# -46342_21-004_3_5.net
KiCad netlist of a schematic drawn in Altium Designer
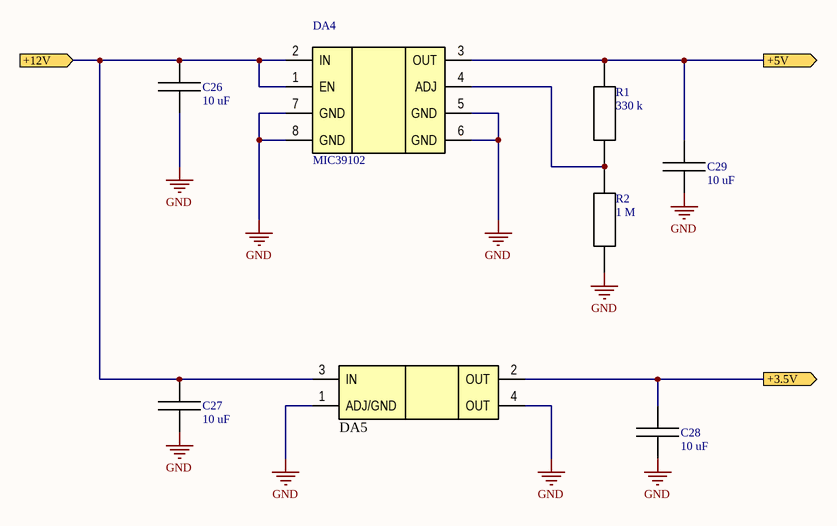
[diagram p0: МПСУ-46342.21-004 Э3 Лист5.SchDoc]

(export (version "E")
  (design (tool "Eeschema 10.0.6"))
  (components
    (comp (ref "C26")
      (value "10 uF")
      (footprint "CAPC100X50X55L20N")
      (description "Capacitor, generic")
      (fields (field (name "TOLERANCE") "5 %"))
      (libsource (lib "receiver") (part "Capacitor"))
    )
    (comp (ref "C27")
      (value "10 uF")
      (footprint "CAPC100X50X55L20N")
      (description "Capacitor, generic")
      (fields (field (name "TOLERANCE") "5 %"))
      (libsource (lib "receiver") (part "Capacitor"))
    )
    (comp (ref "C28")
      (value "10 uF")
      (footprint "CAPC100X50X55L20N")
      (description "Capacitor, generic")
      (fields (field (name "TOLERANCE") "5 %"))
      (libsource (lib "receiver") (part "Capacitor"))
    )
    (comp (ref "C29")
      (value "10 uF")
      (footprint "CAPC100X50X55L20N")
      (description "Capacitor, generic")
      (fields (field (name "TOLERANCE") "5 %"))
      (libsource (lib "receiver") (part "Capacitor"))
    )
    (comp (ref "DA4")
      (value "MIC39102")
      (footprint "SOIC127P600X160-8N")
      (description "1A Low-Voltage Low-Dropout Regulator, Adj")
      (fields (field (name "MANUFACTURER") "Microchip"))
      (libsource (lib "StudentsLibrary") (part "MIC39102"))
    )
    (comp (ref "DA5")
      (value "NCP1117LPST50T3G")
      (footprint "SOT223-4P230_700X180L92X74N")
      (description "1.0 A Low-Dropout Positive\r\nFixed and Adjustable\r\nVoltage Regulators")
      (fields (field (name "MANUFACTURER") "On Semiconductor"))
      (libsource (lib "StudentsLibrary") (part "NCP1117LP"))
    )
    (comp (ref "R1")
      (value "330 k")
      (footprint "RESC100X50X40L25N")
      (description "Resistor, generic")
      (libsource (lib "StudentsLibrary") (part "Resistor"))
    )
    (comp (ref "R2")
      (value "1 M")
      (footprint "RESC100X50X40L25N")
      (description "Resistor, generic")
      (fields (field (name "TOLERANCE") "5 %") (field (name "POWER") "20 V"))
      (libsource (lib "StudentsLibrary") (part "Resistor"))
    )
  )
  (nets
    (net (code "1") (name "/+3.5V") (class "Default")
      (node (ref "C28") (pin "2") (pinfunction "2_2") (pintype "passive"))
      (node (ref "DA5") (pin "2") (pinfunction "OUT_2") (pintype "passive"))
    )
    (net (code "2") (name "/+5V") (class "Default")
      (node (ref "C29") (pin "2") (pinfunction "2_2") (pintype "passive"))
      (node (ref "DA4") (pin "3") (pinfunction "OUT_3") (pintype "passive"))
      (node (ref "R1") (pin "2") (pinfunction "2_2") (pintype "passive"))
    )
    (net (code "3") (name "/+12V") (class "Default")
      (node (ref "C26") (pin "2") (pinfunction "2_2") (pintype "passive"))
      (node (ref "C27") (pin "2") (pinfunction "2_2") (pintype "passive"))
      (node (ref "DA4") (pin "1") (pinfunction "EN_1") (pintype "passive"))
      (node (ref "DA4") (pin "2") (pinfunction "IN_2") (pintype "passive"))
      (node (ref "DA5") (pin "3") (pinfunction "IN_3") (pintype "passive"))
    )
    (net (code "4") (name "GND") (class "Default")
      (node (ref "C26") (pin "1") (pinfunction "1_1") (pintype "passive"))
      (node (ref "C27") (pin "1") (pinfunction "1_1") (pintype "passive"))
      (node (ref "C28") (pin "1") (pinfunction "1_1") (pintype "passive"))
      (node (ref "C29") (pin "1") (pinfunction "1_1") (pintype "passive"))
      (node (ref "DA4") (pin "5") (pinfunction "GND_5") (pintype "passive"))
      (node (ref "DA4") (pin "6") (pinfunction "GND_6") (pintype "passive"))
      (node (ref "DA4") (pin "7") (pinfunction "GND_7") (pintype "passive"))
      (node (ref "DA4") (pin "8") (pinfunction "GND_8") (pintype "passive"))
      (node (ref "DA5") (pin "1") (pinfunction "ADJ/GND_1") (pintype "passive"))
      (node (ref "DA5") (pin "4") (pinfunction "OUT_4") (pintype "passive"))
      (node (ref "R2") (pin "1") (pinfunction "1_1") (pintype "passive"))
    )
    (net (code "5") (name "Net-(DA4-ADJ)") (class "Default")
      (node (ref "DA4") (pin "4") (pinfunction "ADJ_4") (pintype "passive"))
      (node (ref "R1") (pin "1") (pinfunction "1_1") (pintype "passive"))
      (node (ref "R2") (pin "2") (pinfunction "2_2") (pintype "passive"))
    )
  )
)
